# Dashboard_V3.net
KiCad netlist of a schematic drawn in EAGLE
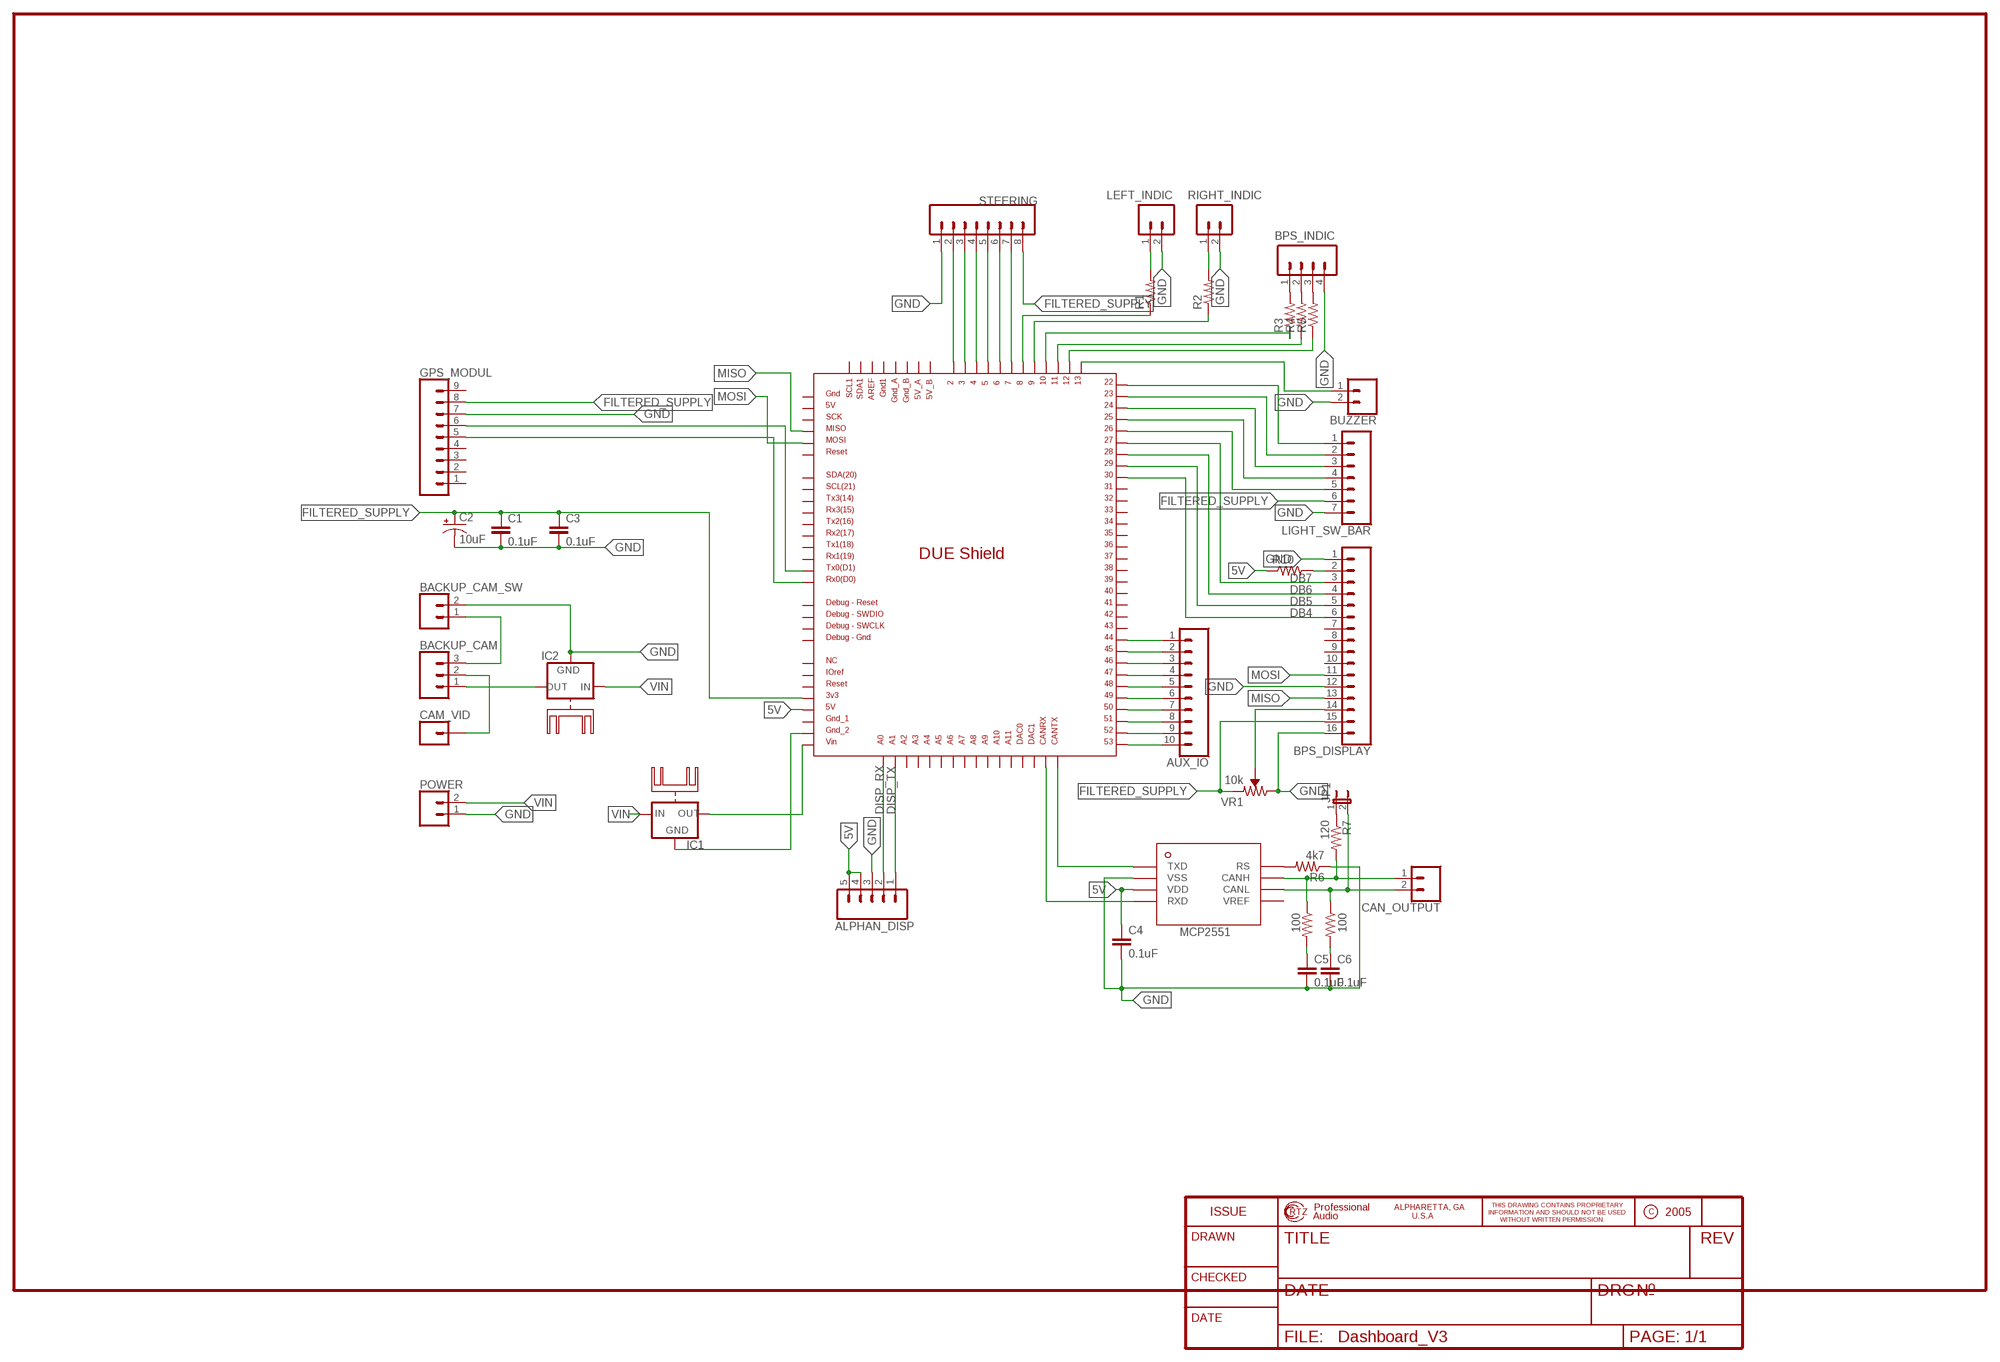
[diagram p0: schematic, sheet 1]

(export (version "E")
  (design (tool "Eeschema 10.0.6"))
  (components
    (comp (ref "ALPHAN_DISP")
      (value "CONN_05")
      (footprint "eagle-import:1X05")
      (libsource (lib "eagle-import") (part "CONN_05"))
    )
    (comp (ref "AUX_IO")
      (value "CONN_10\"")
      (footprint "eagle-import:1X10")
      (libsource (lib "eagle-import") (part "CONN_10{dblquote}"))
    )
    (comp (ref "BACKUP_CAM")
      (value "CONN_03")
      (footprint "eagle-import:1X03")
      (libsource (lib "eagle-import") (part "CONN_03"))
    )
    (comp (ref "BACKUP_CAM_SW")
      (value "CONN_02")
      (footprint "eagle-import:1X02")
      (libsource (lib "eagle-import") (part "CONN_02"))
    )
    (comp (ref "BPS_DISPLAY")
      (value "CONN_16")
      (footprint "eagle-import:1X16")
      (libsource (lib "eagle-import") (part "CONN_16"))
    )
    (comp (ref "BPS_INDIC")
      (value "CONN_04")
      (footprint "eagle-import:1X04")
      (libsource (lib "eagle-import") (part "CONN_04"))
    )
    (comp (ref "BUZZER")
      (value "CONN_02")
      (footprint "eagle-import:1X02")
      (libsource (lib "eagle-import") (part "CONN_02"))
    )
    (comp (ref "C1")
      (value "0.1uF")
      (footprint "eagle-import:C2.5-6")
      (libsource (lib "eagle-import") (part "C2.5/6"))
    )
    (comp (ref "C2")
      (value "10uF")
      (footprint "eagle-import:E5-6")
      (libsource (lib "eagle-import") (part "CPOL-USE5-6"))
    )
    (comp (ref "C3")
      (value "0.1uF")
      (footprint "eagle-import:C2.5-6")
      (libsource (lib "eagle-import") (part "C2.5/6"))
    )
    (comp (ref "C4")
      (value "0.1uF")
      (footprint "eagle-import:C2.5-6")
      (libsource (lib "eagle-import") (part "C2.5/6"))
    )
    (comp (ref "C5")
      (value "0.1uF")
      (footprint "eagle-import:C2.5-6")
      (libsource (lib "eagle-import") (part "C2.5/6"))
    )
    (comp (ref "C6")
      (value "0.1uF")
      (footprint "eagle-import:C2.5-6")
      (libsource (lib "eagle-import") (part "C2.5/6"))
    )
    (comp (ref "CAM_VID")
      (value "CONN_01")
      (footprint "eagle-import:1X01")
      (libsource (lib "eagle-import") (part "CONN_01"))
    )
    (comp (ref "CAN_OUTPUT")
      (value "CONN_025MM")
      (footprint "eagle-import:SCREWTERMINAL-5MM-2")
      (libsource (lib "eagle-import") (part "CONN_025MM"))
    )
    (comp (ref "GPS_MODUL")
      (value "CONN_09")
      (footprint "eagle-import:1X09")
      (libsource (lib "eagle-import") (part "CONN_09"))
    )
    (comp (ref "IC1")
      (value "78XXH")
      (footprint "eagle-import:78XXH")
      (libsource (lib "eagle-import") (part "78XXH"))
    )
    (comp (ref "IC2")
      (value "78XXH")
      (footprint "eagle-import:78XXH")
      (libsource (lib "eagle-import") (part "78XXH"))
    )
    (comp (ref "JP1")
      (value "JP1E")
      (footprint "eagle-import:JP1")
      (libsource (lib "eagle-import") (part "JP1E"))
    )
    (comp (ref "LEFT_INDIC")
      (value "CONN_02")
      (footprint "eagle-import:1X02")
      (libsource (lib "eagle-import") (part "CONN_02"))
    )
    (comp (ref "LIGHT_SW_BAR")
      (value "CONN_07")
      (footprint "eagle-import:1X07")
      (libsource (lib "eagle-import") (part "CONN_07"))
    )
    (comp (ref "POWER")
      (value "CONN_02")
      (footprint "eagle-import:1X02")
      (libsource (lib "eagle-import") (part "CONN_02"))
    )
    (comp (ref "R1")
      (value "R-US_M0805")
      (footprint "eagle-import:M0805")
      (libsource (lib "eagle-import") (part "R-US_M0805"))
    )
    (comp (ref "R2")
      (value "R-US_M0805")
      (footprint "eagle-import:M0805")
      (libsource (lib "eagle-import") (part "R-US_M0805"))
    )
    (comp (ref "R3")
      (value "R-US_M0805")
      (footprint "eagle-import:M0805")
      (libsource (lib "eagle-import") (part "R-US_M0805"))
    )
    (comp (ref "R4")
      (value "R-US_M0805")
      (footprint "eagle-import:M0805")
      (libsource (lib "eagle-import") (part "R-US_M0805"))
    )
    (comp (ref "R5")
      (value "R-US_M0805")
      (footprint "eagle-import:M0805")
      (libsource (lib "eagle-import") (part "R-US_M0805"))
    )
    (comp (ref "R6")
      (value "4k7")
      (footprint "eagle-import:R0805")
      (libsource (lib "eagle-import") (part "R-US_R0805"))
    )
    (comp (ref "R7")
      (value "120")
      (footprint "eagle-import:R0805")
      (libsource (lib "eagle-import") (part "R-US_R0805"))
    )
    (comp (ref "R8")
      (value "100")
      (footprint "eagle-import:R0805")
      (libsource (lib "eagle-import") (part "R-US_R0805"))
    )
    (comp (ref "R9")
      (value "100")
      (footprint "eagle-import:R0805")
      (libsource (lib "eagle-import") (part "R-US_R0805"))
    )
    (comp (ref "R10")
      (value "R-US_R0805")
      (footprint "eagle-import:R0805")
      (libsource (lib "eagle-import") (part "R-US_R0805"))
    )
    (comp (ref "RIGHT_INDIC")
      (value "CONN_02")
      (footprint "eagle-import:1X02")
      (libsource (lib "eagle-import") (part "CONN_02"))
    )
    (comp (ref "STEERING")
      (value "CONN_08\"")
      (footprint "eagle-import:1X08")
      (libsource (lib "eagle-import") (part "CONN_08{dblquote}"))
    )
    (comp (ref "U$1")
      (value "DUE(NORMAL)")
      (footprint "eagle-import:DUE(NORMAL)")
      (libsource (lib "eagle-import") (part "DUE(NORMAL)"))
    )
    (comp (ref "U$2")
      (value "MCP2551")
      (footprint "eagle-import:SOIC-8")
      (libsource (lib "eagle-import") (part "MCP2551"))
    )
    (comp (ref "VR1")
      (value "10k")
      (footprint "eagle-import:TRIMPOT-PTH-3386U")
      (libsource (lib "eagle-import") (part "TRIMPOT-PTH-10MM-KNOB-1/2W-10%"))
    )
  )
  (nets
    (net (code "1") (name "/DB4") (class "Default")
      (node (ref "BPS_DISPLAY") (pin "6") (pinfunction "6_6") (pintype "passive"))
      (node (ref "U$1") (pin "30") (pinfunction "30_30") (pintype "bidirectional"))
    )
    (net (code "2") (name "/DB5") (class "Default")
      (node (ref "BPS_DISPLAY") (pin "5") (pinfunction "5_5") (pintype "passive"))
      (node (ref "U$1") (pin "29") (pinfunction "29_29") (pintype "bidirectional"))
    )
    (net (code "3") (name "/DB6") (class "Default")
      (node (ref "BPS_DISPLAY") (pin "4") (pinfunction "4_4") (pintype "passive"))
      (node (ref "U$1") (pin "28") (pinfunction "28_28") (pintype "bidirectional"))
    )
    (net (code "4") (name "/DB7") (class "Default")
      (node (ref "BPS_DISPLAY") (pin "3") (pinfunction "3_3") (pintype "passive"))
      (node (ref "U$1") (pin "27") (pinfunction "27_27") (pintype "bidirectional"))
    )
    (net (code "5") (name "/DISP_RX") (class "Default")
      (node (ref "ALPHAN_DISP") (pin "2") (pinfunction "2_2") (pintype "passive"))
      (node (ref "U$1") (pin "A0") (pinfunction "A0_A0") (pintype "bidirectional"))
    )
    (net (code "6") (name "/DISP_TX") (class "Default")
      (node (ref "ALPHAN_DISP") (pin "1") (pinfunction "1_1") (pintype "passive"))
      (node (ref "U$1") (pin "A1") (pinfunction "A1_A1") (pintype "bidirectional"))
    )
    (net (code "7") (name "5V") (class "Default")
      (node (ref "ALPHAN_DISP") (pin "4") (pinfunction "4_4") (pintype "passive"))
      (node (ref "ALPHAN_DISP") (pin "5") (pinfunction "5_5") (pintype "passive"))
      (node (ref "C4") (pin "1") (pinfunction "1_1") (pintype "passive"))
      (node (ref "R10") (pin "1") (pinfunction "1_1") (pintype "passive"))
      (node (ref "U$1") (pin "5V") (pinfunction "5V_5V") (pintype "bidirectional"))
      (node (ref "U$2") (pin "VDD") (pinfunction "VDD_VDD") (pintype "bidirectional"))
    )
    (net (code "8") (name "FILTERED_SUPPLY") (class "Default")
      (node (ref "BPS_DISPLAY") (pin "15") (pinfunction "15_15") (pintype "passive"))
      (node (ref "C1") (pin "1") (pinfunction "1_1") (pintype "passive"))
      (node (ref "C2") (pin "+") (pinfunction "+_+") (pintype "passive"))
      (node (ref "C3") (pin "1") (pinfunction "1_1") (pintype "passive"))
      (node (ref "GPS_MODUL") (pin "8") (pinfunction "8_8") (pintype "passive"))
      (node (ref "LIGHT_SW_BAR") (pin "6") (pinfunction "6_6") (pintype "passive"))
      (node (ref "STEERING") (pin "8") (pinfunction "8_8") (pintype "passive"))
      (node (ref "U$1") (pin "3V3") (pinfunction "3V3_3V3") (pintype "bidirectional"))
      (node (ref "VR1") (pin "1") (pinfunction "CCW_1") (pintype "passive"))
    )
    (net (code "9") (name "GND") (class "Default")
      (node (ref "ALPHAN_DISP") (pin "3") (pinfunction "3_3") (pintype "passive"))
      (node (ref "BACKUP_CAM_SW") (pin "2") (pinfunction "2_2") (pintype "passive"))
      (node (ref "BPS_DISPLAY") (pin "1") (pinfunction "1_1") (pintype "passive"))
      (node (ref "BPS_DISPLAY") (pin "12") (pinfunction "12_12") (pintype "passive"))
      (node (ref "BPS_DISPLAY") (pin "16") (pinfunction "16_16") (pintype "passive"))
      (node (ref "BPS_INDIC") (pin "4") (pinfunction "4_4") (pintype "passive"))
      (node (ref "BUZZER") (pin "2") (pinfunction "2_2") (pintype "passive"))
      (node (ref "C1") (pin "2") (pinfunction "2_2") (pintype "passive"))
      (node (ref "C2") (pin "-") (pinfunction "-_-") (pintype "passive"))
      (node (ref "C3") (pin "2") (pinfunction "2_2") (pintype "passive"))
      (node (ref "C4") (pin "2") (pinfunction "2_2") (pintype "passive"))
      (node (ref "C5") (pin "2") (pinfunction "2_2") (pintype "passive"))
      (node (ref "C6") (pin "2") (pinfunction "2_2") (pintype "passive"))
      (node (ref "GPS_MODUL") (pin "7") (pinfunction "7_7") (pintype "passive"))
      (node (ref "IC2") (pin "GND") (pinfunction "GND_GND") (pintype "input"))
      (node (ref "LEFT_INDIC") (pin "2") (pinfunction "2_2") (pintype "passive"))
      (node (ref "LIGHT_SW_BAR") (pin "7") (pinfunction "7_7") (pintype "passive"))
      (node (ref "POWER") (pin "1") (pinfunction "1_1") (pintype "passive"))
      (node (ref "R6") (pin "1") (pinfunction "1_1") (pintype "passive"))
      (node (ref "RIGHT_INDIC") (pin "2") (pinfunction "2_2") (pintype "passive"))
      (node (ref "STEERING") (pin "1") (pinfunction "1_1") (pintype "passive"))
      (node (ref "U$2") (pin "VSS") (pinfunction "VSS_VSS") (pintype "bidirectional"))
      (node (ref "VR1") (pin "3") (pinfunction "CW_3") (pintype "passive"))
    )
    (net (code "10") (name "MISO") (class "Default")
      (node (ref "BPS_DISPLAY") (pin "13") (pinfunction "13_13") (pintype "passive"))
      (node (ref "U$1") (pin "MISO_ICSP") (pinfunction "MISO_ICSP_MISO_ICSP") (pintype "bidirectional"))
    )
    (net (code "11") (name "MOSI") (class "Default")
      (node (ref "BPS_DISPLAY") (pin "11") (pinfunction "11_11") (pintype "passive"))
      (node (ref "U$1") (pin "MOSI_ICSP") (pinfunction "MOSI_ICSP_MOSI_ICSP") (pintype "bidirectional"))
    )
    (net (code "12") (name "Net-(AUX_IO-Pad1)") (class "Default")
      (node (ref "AUX_IO") (pin "1") (pinfunction "1_1") (pintype "passive"))
      (node (ref "U$1") (pin "44") (pinfunction "44_44") (pintype "bidirectional"))
    )
    (net (code "13") (name "Net-(AUX_IO-Pad2)") (class "Default")
      (node (ref "AUX_IO") (pin "2") (pinfunction "2_2") (pintype "passive"))
      (node (ref "U$1") (pin "45") (pinfunction "45_45") (pintype "bidirectional"))
    )
    (net (code "14") (name "Net-(AUX_IO-Pad3)") (class "Default")
      (node (ref "AUX_IO") (pin "3") (pinfunction "3_3") (pintype "passive"))
      (node (ref "U$1") (pin "46") (pinfunction "46_46") (pintype "bidirectional"))
    )
    (net (code "15") (name "Net-(AUX_IO-Pad4)") (class "Default")
      (node (ref "AUX_IO") (pin "4") (pinfunction "4_4") (pintype "passive"))
      (node (ref "U$1") (pin "47") (pinfunction "47_47") (pintype "bidirectional"))
    )
    (net (code "16") (name "Net-(AUX_IO-Pad5)") (class "Default")
      (node (ref "AUX_IO") (pin "5") (pinfunction "5_5") (pintype "passive"))
      (node (ref "U$1") (pin "48") (pinfunction "48_48") (pintype "bidirectional"))
    )
    (net (code "17") (name "Net-(AUX_IO-Pad6)") (class "Default")
      (node (ref "AUX_IO") (pin "6") (pinfunction "6_6") (pintype "passive"))
      (node (ref "U$1") (pin "49") (pinfunction "49_49") (pintype "bidirectional"))
    )
    (net (code "18") (name "Net-(AUX_IO-Pad7)") (class "Default")
      (node (ref "AUX_IO") (pin "7") (pinfunction "7_7") (pintype "passive"))
      (node (ref "U$1") (pin "50") (pinfunction "50_50") (pintype "bidirectional"))
    )
    (net (code "19") (name "Net-(AUX_IO-Pad8)") (class "Default")
      (node (ref "AUX_IO") (pin "8") (pinfunction "8_8") (pintype "passive"))
      (node (ref "U$1") (pin "51") (pinfunction "51_51") (pintype "bidirectional"))
    )
    (net (code "20") (name "Net-(AUX_IO-Pad9)") (class "Default")
      (node (ref "AUX_IO") (pin "9") (pinfunction "9_9") (pintype "passive"))
      (node (ref "U$1") (pin "52") (pinfunction "52_52") (pintype "bidirectional"))
    )
    (net (code "21") (name "Net-(AUX_IO-Pad10)") (class "Default")
      (node (ref "AUX_IO") (pin "10") (pinfunction "10_10") (pintype "passive"))
      (node (ref "U$1") (pin "53") (pinfunction "53_53") (pintype "bidirectional"))
    )
    (net (code "22") (name "Net-(BACKUP_CAM-Pad1)") (class "Default")
      (node (ref "BACKUP_CAM") (pin "1") (pinfunction "1_1") (pintype "passive"))
      (node (ref "IC2") (pin "OUT") (pinfunction "OUT_OUT") (pintype "passive"))
    )
    (net (code "23") (name "Net-(BACKUP_CAM-Pad2)") (class "Default")
      (node (ref "BACKUP_CAM") (pin "2") (pinfunction "2_2") (pintype "passive"))
      (node (ref "CAM_VID") (pin "1") (pinfunction "1_1") (pintype "passive"))
    )
    (net (code "24") (name "Net-(BACKUP_CAM-Pad3)") (class "Default")
      (node (ref "BACKUP_CAM") (pin "3") (pinfunction "3_3") (pintype "passive"))
      (node (ref "BACKUP_CAM_SW") (pin "1") (pinfunction "1_1") (pintype "passive"))
    )
    (net (code "25") (name "Net-(BPS_DISPLAY-Pad2)") (class "Default")
      (node (ref "BPS_DISPLAY") (pin "2") (pinfunction "2_2") (pintype "passive"))
      (node (ref "R10") (pin "2") (pinfunction "2_2") (pintype "passive"))
    )
    (net (code "26") (name "Net-(BPS_INDIC-Pad1)") (class "Default")
      (node (ref "BPS_INDIC") (pin "1") (pinfunction "1_1") (pintype "passive"))
      (node (ref "R3") (pin "2") (pinfunction "2_2") (pintype "passive"))
    )
    (net (code "27") (name "Net-(BPS_INDIC-Pad2)") (class "Default")
      (node (ref "BPS_INDIC") (pin "2") (pinfunction "2_2") (pintype "passive"))
      (node (ref "R4") (pin "2") (pinfunction "2_2") (pintype "passive"))
    )
    (net (code "28") (name "Net-(BPS_INDIC-Pad3)") (class "Default")
      (node (ref "BPS_INDIC") (pin "3") (pinfunction "3_3") (pintype "passive"))
      (node (ref "R5") (pin "2") (pinfunction "2_2") (pintype "passive"))
    )
    (net (code "29") (name "Net-(BUZZER-Pad1)") (class "Default")
      (node (ref "BUZZER") (pin "1") (pinfunction "1_1") (pintype "passive"))
      (node (ref "U$1") (pin "13") (pinfunction "13_13") (pintype "bidirectional"))
    )
    (net (code "30") (name "Net-(C5-Pad1)") (class "Default")
      (node (ref "C5") (pin "1") (pinfunction "1_1") (pintype "passive"))
      (node (ref "R8") (pin "2") (pinfunction "2_2") (pintype "passive"))
    )
    (net (code "31") (name "Net-(C6-Pad1)") (class "Default")
      (node (ref "C6") (pin "1") (pinfunction "1_1") (pintype "passive"))
      (node (ref "R9") (pin "2") (pinfunction "2_2") (pintype "passive"))
    )
    (net (code "32") (name "Net-(CAN_OUTPUT-Pad1)") (class "Default")
      (node (ref "CAN_OUTPUT") (pin "1") (pinfunction "1_1") (pintype "passive"))
      (node (ref "R7") (pin "2") (pinfunction "2_2") (pintype "passive"))
      (node (ref "R8") (pin "1") (pinfunction "1_1") (pintype "passive"))
      (node (ref "U$2") (pin "CANH") (pinfunction "CANH_CANH") (pintype "bidirectional"))
    )
    (net (code "33") (name "Net-(CAN_OUTPUT-Pad2)") (class "Default")
      (node (ref "CAN_OUTPUT") (pin "2") (pinfunction "2_2") (pintype "passive"))
      (node (ref "JP1") (pin "2") (pinfunction "2_2") (pintype "passive"))
      (node (ref "R9") (pin "1") (pinfunction "1_1") (pintype "passive"))
      (node (ref "U$2") (pin "CANL") (pinfunction "CANL_CANL") (pintype "bidirectional"))
    )
    (net (code "34") (name "Net-(GPS_MODUL-Pad5)") (class "Default")
      (node (ref "GPS_MODUL") (pin "5") (pinfunction "5_5") (pintype "passive"))
      (node (ref "U$1") (pin "RX0") (pinfunction "RX0_RX0") (pintype "bidirectional"))
    )
    (net (code "35") (name "Net-(GPS_MODUL-Pad6)") (class "Default")
      (node (ref "GPS_MODUL") (pin "6") (pinfunction "6_6") (pintype "passive"))
      (node (ref "U$1") (pin "TX0") (pinfunction "TX0_TX0") (pintype "bidirectional"))
    )
    (net (code "36") (name "Net-(IC1-PadGND)") (class "Default")
      (node (ref "IC1") (pin "GND") (pinfunction "GND_GND") (pintype "input"))
      (node (ref "U$1") (pin "GND_2") (pinfunction "GND_2_GND_2") (pintype "bidirectional"))
    )
    (net (code "37") (name "Net-(IC1-PadOUT)") (class "Default")
      (node (ref "IC1") (pin "OUT") (pinfunction "OUT_OUT") (pintype "passive"))
      (node (ref "U$1") (pin "VIN") (pinfunction "VIN_VIN") (pintype "bidirectional"))
    )
    (net (code "38") (name "Net-(JP1-Pad1)") (class "Default")
      (node (ref "JP1") (pin "1") (pinfunction "1_1") (pintype "passive"))
      (node (ref "R7") (pin "1") (pinfunction "1_1") (pintype "passive"))
    )
    (net (code "39") (name "Net-(LEFT_INDIC-Pad1)") (class "Default")
      (node (ref "LEFT_INDIC") (pin "1") (pinfunction "1_1") (pintype "passive"))
      (node (ref "R1") (pin "2") (pinfunction "2_2") (pintype "passive"))
    )
    (net (code "40") (name "Net-(LIGHT_SW_BAR-Pad1)") (class "Default")
      (node (ref "LIGHT_SW_BAR") (pin "1") (pinfunction "1_1") (pintype "passive"))
      (node (ref "U$1") (pin "22") (pinfunction "22_22") (pintype "bidirectional"))
    )
    (net (code "41") (name "Net-(LIGHT_SW_BAR-Pad2)") (class "Default")
      (node (ref "LIGHT_SW_BAR") (pin "2") (pinfunction "2_2") (pintype "passive"))
      (node (ref "U$1") (pin "23") (pinfunction "23_23") (pintype "bidirectional"))
    )
    (net (code "42") (name "Net-(LIGHT_SW_BAR-Pad3)") (class "Default")
      (node (ref "LIGHT_SW_BAR") (pin "3") (pinfunction "3_3") (pintype "passive"))
      (node (ref "U$1") (pin "24") (pinfunction "24_24") (pintype "bidirectional"))
    )
    (net (code "43") (name "Net-(LIGHT_SW_BAR-Pad4)") (class "Default")
      (node (ref "LIGHT_SW_BAR") (pin "4") (pinfunction "4_4") (pintype "passive"))
      (node (ref "U$1") (pin "25") (pinfunction "25_25") (pintype "bidirectional"))
    )
    (net (code "44") (name "Net-(LIGHT_SW_BAR-Pad5)") (class "Default")
      (node (ref "LIGHT_SW_BAR") (pin "5") (pinfunction "5_5") (pintype "passive"))
      (node (ref "U$1") (pin "26") (pinfunction "26_26") (pintype "bidirectional"))
    )
    (net (code "45") (name "Net-(R1-Pad1)") (class "Default")
      (node (ref "R1") (pin "1") (pinfunction "1_1") (pintype "passive"))
      (node (ref "U$1") (pin "8") (pinfunction "8_8") (pintype "bidirectional"))
    )
    (net (code "46") (name "Net-(R2-Pad1)") (class "Default")
      (node (ref "R2") (pin "1") (pinfunction "1_1") (pintype "passive"))
      (node (ref "U$1") (pin "9") (pinfunction "9_9") (pintype "bidirectional"))
    )
    (net (code "47") (name "Net-(R2-Pad2)") (class "Default")
      (node (ref "R2") (pin "2") (pinfunction "2_2") (pintype "passive"))
      (node (ref "RIGHT_INDIC") (pin "1") (pinfunction "1_1") (pintype "passive"))
    )
    (net (code "48") (name "Net-(R3-Pad1)") (class "Default")
      (node (ref "R3") (pin "1") (pinfunction "1_1") (pintype "passive"))
      (node (ref "U$1") (pin "10") (pinfunction "10_10") (pintype "bidirectional"))
    )
    (net (code "49") (name "Net-(R4-Pad1)") (class "Default")
      (node (ref "R4") (pin "1") (pinfunction "1_1") (pintype "passive"))
      (node (ref "U$1") (pin "11") (pinfunction "11_11") (pintype "bidirectional"))
    )
    (net (code "50") (name "Net-(R5-Pad1)") (class "Default")
      (node (ref "R5") (pin "1") (pinfunction "1_1") (pintype "passive"))
      (node (ref "U$1") (pin "12") (pinfunction "12_12") (pintype "bidirectional"))
    )
    (net (code "51") (name "Net-(R6-Pad2)") (class "Default")
      (node (ref "R6") (pin "2") (pinfunction "2_2") (pintype "passive"))
      (node (ref "U$2") (pin "RS") (pinfunction "RS_RS") (pintype "bidirectional"))
    )
    (net (code "52") (name "Net-(STEERING-Pad2)") (class "Default")
      (node (ref "STEERING") (pin "2") (pinfunction "2_2") (pintype "passive"))
      (node (ref "U$1") (pin "2") (pinfunction "2_2") (pintype "bidirectional"))
    )
    (net (code "53") (name "Net-(STEERING-Pad3)") (class "Default")
      (node (ref "STEERING") (pin "3") (pinfunction "3_3") (pintype "passive"))
      (node (ref "U$1") (pin "3") (pinfunction "3_3") (pintype "bidirectional"))
    )
    (net (code "54") (name "Net-(STEERING-Pad4)") (class "Default")
      (node (ref "STEERING") (pin "4") (pinfunction "4_4") (pintype "passive"))
      (node (ref "U$1") (pin "4") (pinfunction "4_4") (pintype "bidirectional"))
    )
    (net (code "55") (name "Net-(STEERING-Pad5)") (class "Default")
      (node (ref "STEERING") (pin "5") (pinfunction "5_5") (pintype "passive"))
      (node (ref "U$1") (pin "5") (pinfunction "5_5") (pintype "bidirectional"))
    )
    (net (code "56") (name "Net-(STEERING-Pad6)") (class "Default")
      (node (ref "STEERING") (pin "6") (pinfunction "6_6") (pintype "passive"))
      (node (ref "U$1") (pin "6") (pinfunction "6_6") (pintype "bidirectional"))
    )
    (net (code "57") (name "Net-(STEERING-Pad7)") (class "Default")
      (node (ref "STEERING") (pin "7") (pinfunction "7_7") (pintype "passive"))
      (node (ref "U$1") (pin "7") (pinfunction "7_7") (pintype "bidirectional"))
    )
    (net (code "58") (name "Net-(U$1-PadCANRX)") (class "Default")
      (node (ref "U$1") (pin "CANRX") (pinfunction "CANRX_CANRX") (pintype "bidirectional"))
      (node (ref "U$2") (pin "RXD") (pinfunction "RXD_RXD") (pintype "bidirectional"))
    )
    (net (code "59") (name "Net-(U$1-PadCANTX)") (class "Default")
      (node (ref "U$1") (pin "CANTX") (pinfunction "CANTX_CANTX") (pintype "bidirectional"))
      (node (ref "U$2") (pin "TXD") (pinfunction "TXD_TXD") (pintype "bidirectional"))
    )
    (net (code "60") (name "Net-(VR1-WIPER)") (class "Default")
      (node (ref "BPS_DISPLAY") (pin "14") (pinfunction "14_14") (pintype "passive"))
      (node (ref "VR1") (pin "2") (pinfunction "WIPER_2") (pintype "passive"))
    )
    (net (code "61") (name "VIN") (class "Default")
      (node (ref "IC1") (pin "IN") (pinfunction "IN_IN") (pintype "input"))
      (node (ref "IC2") (pin "IN") (pinfunction "IN_IN") (pintype "input"))
      (node (ref "POWER") (pin "2") (pinfunction "2_2") (pintype "passive"))
    )
    (net (code "62") (name "unconnected-(BPS_DISPLAY-Pad7)") (class "Default")
      (node (ref "BPS_DISPLAY") (pin "7") (pinfunction "7_7") (pintype "passive"))
    )
    (net (code "63") (name "unconnected-(BPS_DISPLAY-Pad8)") (class "Default")
      (node (ref "BPS_DISPLAY") (pin "8") (pinfunction "8_8") (pintype "passive"))
    )
    (net (code "64") (name "unconnected-(BPS_DISPLAY-Pad9)") (class "Default")
      (node (ref "BPS_DISPLAY") (pin "9") (pinfunction "9_9") (pintype "passive"))
    )
    (net (code "65") (name "unconnected-(BPS_DISPLAY-Pad10)") (class "Default")
      (node (ref "BPS_DISPLAY") (pin "10") (pinfunction "10_10") (pintype "passive"))
    )
    (net (code "66") (name "unconnected-(GPS_MODUL-Pad1)") (class "Default")
      (node (ref "GPS_MODUL") (pin "1") (pinfunction "1_1") (pintype "passive"))
    )
    (net (code "67") (name "unconnected-(GPS_MODUL-Pad2)") (class "Default")
      (node (ref "GPS_MODUL") (pin "2") (pinfunction "2_2") (pintype "passive"))
    )
    (net (code "68") (name "unconnected-(GPS_MODUL-Pad3)") (class "Default")
      (node (ref "GPS_MODUL") (pin "3") (pinfunction "3_3") (pintype "passive"))
    )
    (net (code "69") (name "unconnected-(GPS_MODUL-Pad4)") (class "Default")
      (node (ref "GPS_MODUL") (pin "4") (pinfunction "4_4") (pintype "passive"))
    )
    (net (code "70") (name "unconnected-(GPS_MODUL-Pad9)") (class "Default")
      (node (ref "GPS_MODUL") (pin "9") (pinfunction "9_9") (pintype "passive"))
    )
    (net (code "71") (name "unconnected-(U$1-Pad5V_A)") (class "Default")
      (node (ref "U$1") (pin "5V_A") (pinfunction "5V_A_5V_A") (pintype "bidirectional"))
    )
    (net (code "72") (name "unconnected-(U$1-Pad5V_B)") (class "Default")
      (node (ref "U$1") (pin "5V_B") (pinfunction "5V_B_5V_B") (pintype "bidirectional"))
    )
    (net (code "73") (name "unconnected-(U$1-Pad5V_ICSP)") (class "Default")
      (node (ref "U$1") (pin "5V_ICSP") (pinfunction "5V_ICSP_5V_ICSP") (pintype "bidirectional"))
    )
    (net (code "74") (name "unconnected-(U$1-Pad31)") (class "Default")
      (node (ref "U$1") (pin "31") (pinfunction "31_31") (pintype "bidirectional"))
    )
    (net (code "75") (name "unconnected-(U$1-Pad32)") (class "Default")
      (node (ref "U$1") (pin "32") (pinfunction "32_32") (pintype "bidirectional"))
    )
    (net (code "76") (name "unconnected-(U$1-Pad33)") (class "Default")
      (node (ref "U$1") (pin "33") (pinfunction "33_33") (pintype "bidirectional"))
    )
    (net (code "77") (name "unconnected-(U$1-Pad34)") (class "Default")
      (node (ref "U$1") (pin "34") (pinfunction "34_34") (pintype "bidirectional"))
    )
    (net (code "78") (name "unconnected-(U$1-Pad35)") (class "Default")
      (node (ref "U$1") (pin "35") (pinfunction "35_35") (pintype "bidirectional"))
    )
    (net (code "79") (name "unconnected-(U$1-Pad36)") (class "Default")
      (node (ref "U$1") (pin "36") (pinfunction "36_36") (pintype "bidirectional"))
    )
    (net (code "80") (name "unconnected-(U$1-Pad37)") (class "Default")
      (node (ref "U$1") (pin "37") (pinfunction "37_37") (pintype "bidirectional"))
    )
    (net (code "81") (name "unconnected-(U$1-Pad38)") (class "Default")
      (node (ref "U$1") (pin "38") (pinfunction "38_38") (pintype "bidirectional"))
    )
    (net (code "82") (name "unconnected-(U$1-Pad39)") (class "Default")
      (node (ref "U$1") (pin "39") (pinfunction "39_39") (pintype "bidirectional"))
    )
    (net (code "83") (name "unconnected-(U$1-Pad40)") (class "Default")
      (node (ref "U$1") (pin "40") (pinfunction "40_40") (pintype "bidirectional"))
    )
    (net (code "84") (name "unconnected-(U$1-Pad41)") (class "Default")
      (node (ref "U$1") (pin "41") (pinfunction "41_41") (pintype "bidirectional"))
    )
    (net (code "85") (name "unconnected-(U$1-Pad42)") (class "Default")
      (node (ref "U$1") (pin "42") (pinfunction "42_42") (pintype "bidirectional"))
    )
    (net (code "86") (name "unconnected-(U$1-Pad43)") (class "Default")
      (node (ref "U$1") (pin "43") (pinfunction "43_43") (pintype "bidirectional"))
    )
    (net (code "87") (name "unconnected-(U$1-PadA2)") (class "Default")
      (node (ref "U$1") (pin "A2") (pinfunction "A2_A2") (pintype "bidirectional"))
    )
    (net (code "88") (name "unconnected-(U$1-PadA3)") (class "Default")
      (node (ref "U$1") (pin "A3") (pinfunction "A3_A3") (pintype "bidirectional"))
    )
    (net (code "89") (name "unconnected-(U$1-PadA4)") (class "Default")
      (node (ref "U$1") (pin "A4") (pinfunction "A4_A4") (pintype "bidirectional"))
    )
    (net (code "90") (name "unconnected-(U$1-PadA5)") (class "Default")
      (node (ref "U$1") (pin "A5") (pinfunction "A5_A5") (pintype "bidirectional"))
    )
    (net (code "91") (name "unconnected-(U$1-PadA6)") (class "Default")
      (node (ref "U$1") (pin "A6") (pinfunction "A6_A6") (pintype "bidirectional"))
    )
    (net (code "92") (name "unconnected-(U$1-PadA7)") (class "Default")
      (node (ref "U$1") (pin "A7") (pinfunction "A7_A7") (pintype "bidirectional"))
    )
    (net (code "93") (name "unconnected-(U$1-PadA8)") (class "Default")
      (node (ref "U$1") (pin "A8") (pinfunction "A8_A8") (pintype "bidirectional"))
    )
    (net (code "94") (name "unconnected-(U$1-PadA9)") (class "Default")
      (node (ref "U$1") (pin "A9") (pinfunction "A9_A9") (pintype "bidirectional"))
    )
    (net (code "95") (name "unconnected-(U$1-PadA10)") (class "Default")
      (node (ref "U$1") (pin "A10") (pinfunction "A10_A10") (pintype "bidirectional"))
    )
    (net (code "96") (name "unconnected-(U$1-PadA11)") (class "Default")
      (node (ref "U$1") (pin "A11") (pinfunction "A11_A11") (pintype "bidirectional"))
    )
    (net (code "97") (name "unconnected-(U$1-PadAREF)") (class "Default")
      (node (ref "U$1") (pin "AREF") (pinfunction "AREF_AREF") (pintype "bidirectional"))
    )
    (net (code "98") (name "unconnected-(U$1-PadDAC0)") (class "Default")
      (node (ref "U$1") (pin "DAC0") (pinfunction "DAC0_DAC0") (pintype "bidirectional"))
    )
    (net (code "99") (name "unconnected-(U$1-PadDAC1)") (class "Default")
      (node (ref "U$1") (pin "DAC1") (pinfunction "DAC1_DAC1") (pintype "bidirectional"))
    )
    (net (code "100") (name "unconnected-(U$1-PadGND1)") (class "Default")
      (node (ref "U$1") (pin "GND1") (pinfunction "GND1_GND1") (pintype "bidirectional"))
    )
    (net (code "101") (name "unconnected-(U$1-PadGND_1)") (class "Default")
      (node (ref "U$1") (pin "GND_1") (pinfunction "GND_1_GND_1") (pintype "bidirectional"))
    )
    (net (code "102") (name "unconnected-(U$1-PadGND_A)") (class "Default")
      (node (ref "U$1") (pin "GND_A") (pinfunction "GND_A_GND_A") (pintype "bidirectional"))
    )
    (net (code "103") (name "unconnected-(U$1-PadGND_B)") (class "Default")
      (node (ref "U$1") (pin "GND_B") (pinfunction "GND_B_GND_B") (pintype "bidirectional"))
    )
    (net (code "104") (name "unconnected-(U$1-PadGND_DEBUG)") (class "Default")
      (node (ref "U$1") (pin "GND_DEBUG") (pinfunction "GND_DEBUG_GND_DEBUG") (pintype "bidirectional"))
    )
    (net (code "105") (name "unconnected-(U$1-PadGND_ICSP)") (class "Default")
      (node (ref "U$1") (pin "GND_ICSP") (pinfunction "GND_ICSP_GND_ICSP") (pintype "bidirectional"))
    )
    (net (code "106") (name "unconnected-(U$1-PadIOREF)") (class "Default")
      (node (ref "U$1") (pin "IOREF") (pinfunction "IOREF_IOREF") (pintype "bidirectional"))
    )
    (net (code "107") (name "unconnected-(U$1-PadNC)") (class "Default")
      (node (ref "U$1") (pin "NC") (pinfunction "NC_NC") (pintype "bidirectional"))
    )
    (net (code "108") (name "unconnected-(U$1-PadRESET)") (class "Default")
      (node (ref "U$1") (pin "RESET") (pinfunction "RESET_RESET") (pintype "bidirectional"))
    )
    (net (code "109") (name "unconnected-(U$1-PadRESET_DEBUG)") (class "Default")
      (node (ref "U$1") (pin "RESET_DEBUG") (pinfunction "RESET_DEBUG_RESET_DEBUG") (pintype "bidirectional"))
    )
    (net (code "110") (name "unconnected-(U$1-PadRESET_ICSP)") (class "Default")
      (node (ref "U$1") (pin "RESET_ICSP") (pinfunction "RESET_ICSP_RESET_ICSP") (pintype "bidirectional"))
    )
    (net (code "111") (name "unconnected-(U$1-PadRX1)") (class "Default")
      (node (ref "U$1") (pin "RX1") (pinfunction "RX1_RX1") (pintype "bidirectional"))
    )
    (net (code "112") (name "unconnected-(U$1-PadRX2)") (class "Default")
      (node (ref "U$1") (pin "RX2") (pinfunction "RX2_RX2") (pintype "bidirectional"))
    )
    (net (code "113") (name "unconnected-(U$1-PadRX3)") (class "Default")
      (node (ref "U$1") (pin "RX3") (pinfunction "RX3_RX3") (pintype "bidirectional"))
    )
    (net (code "114") (name "unconnected-(U$1-PadSCK_ICSP)") (class "Default")
      (node (ref "U$1") (pin "SCK_ICSP") (pinfunction "SCK_ICSP_SCK_ICSP") (pintype "bidirectional"))
    )
    (net (code "115") (name "unconnected-(U$1-PadSCL)") (class "Default")
      (node (ref "U$1") (pin "SCL") (pinfunction "SCL_SCL") (pintype "bidirectional"))
    )
    (net (code "116") (name "unconnected-(U$1-PadSCL1)") (class "Default")
      (node (ref "U$1") (pin "SCL1") (pinfunction "SCL1_SCL1") (pintype "bidirectional"))
    )
    (net (code "117") (name "unconnected-(U$1-PadSDA)") (class "Default")
      (node (ref "U$1") (pin "SDA") (pinfunction "SDA_SDA") (pintype "bidirectional"))
    )
    (net (code "118") (name "unconnected-(U$1-PadSDA1)") (class "Default")
      (node (ref "U$1") (pin "SDA1") (pinfunction "SDA1_SDA1") (pintype "bidirectional"))
    )
    (net (code "119") (name "unconnected-(U$1-PadSWCLK_DEBUG)") (class "Default")
      (node (ref "U$1") (pin "SWCLK_DEBUG") (pinfunction "SWCLK_DEBUG_SWCLK_DEBUG") (pintype "bidirectional"))
    )
    (net (code "120") (name "unconnected-(U$1-PadSWDIO_DEBUG)") (class "Default")
      (node (ref "U$1") (pin "SWDIO_DEBUG") (pinfunction "SWDIO_DEBUG_SWDIO_DEBUG") (pintype "bidirectional"))
    )
    (net (code "121") (name "unconnected-(U$1-PadTX1)") (class "Default")
      (node (ref "U$1") (pin "TX1") (pinfunction "TX1_TX1") (pintype "bidirectional"))
    )
    (net (code "122") (name "unconnected-(U$1-PadTX2)") (class "Default")
      (node (ref "U$1") (pin "TX2") (pinfunction "TX2_TX2") (pintype "bidirectional"))
    )
    (net (code "123") (name "unconnected-(U$1-PadTX3)") (class "Default")
      (node (ref "U$1") (pin "TX3") (pinfunction "TX3_TX3") (pintype "bidirectional"))
    )
    (net (code "124") (name "unconnected-(U$2-PadVREF)") (class "Default")
      (node (ref "U$2") (pin "VREF") (pinfunction "VREF_VREF") (pintype "bidirectional"))
    )
  )
)
